# DRIVER.net
KiCad netlist of a schematic drawn in Altium Designer
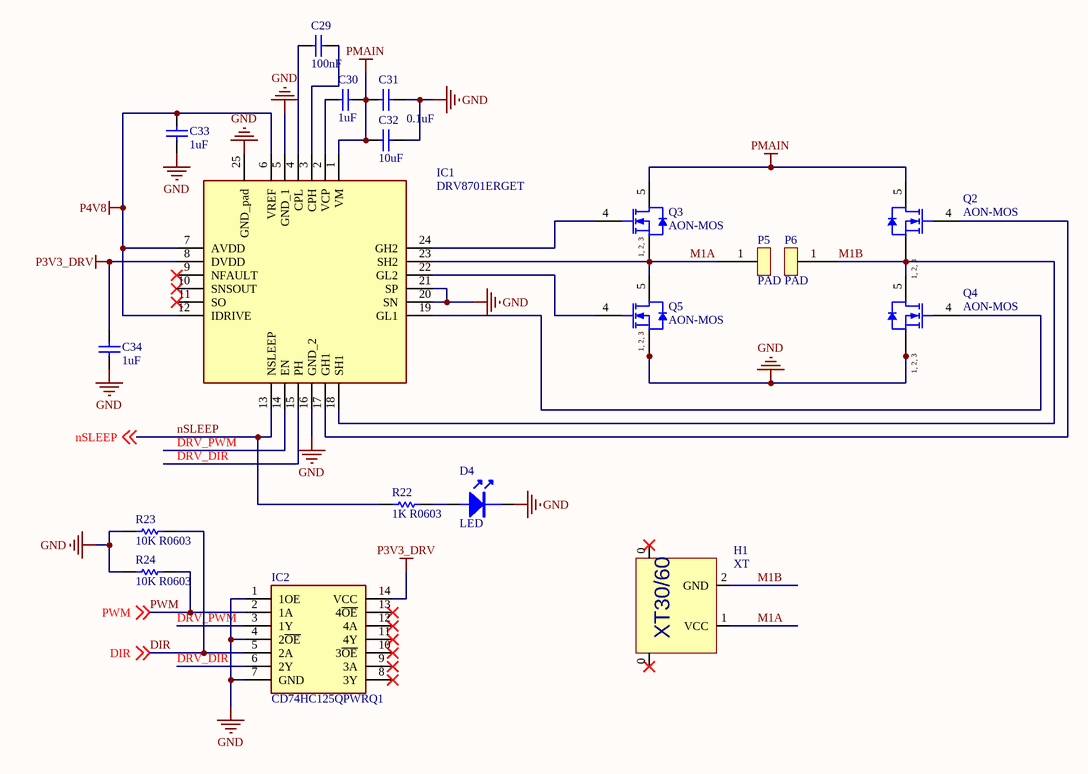
[diagram p0: DRIVER.SchDoc]

(export (version "E")
  (design (tool "Eeschema 10.0.6"))
  (components
    (comp (ref "C29")
      (value "100nF")
      (footprint "0603_C")
      (description "Capacitor")
      (fields (field (name "PUBLISHER") "Altium Limited"))
      (libsource (lib "My Footprint") (part "CAP"))
    )
    (comp (ref "C30")
      (value "1uF")
      (footprint "0603_C")
      (description "Capacitor")
      (fields (field (name "PUBLISHER") "Altium Limited"))
      (libsource (lib "My Footprint") (part "CAP"))
    )
    (comp (ref "C31")
      (value "0.1uF")
      (footprint "0603_C")
      (description "Capacitor")
      (fields (field (name "PUBLISHER") "Altium Limited"))
      (libsource (lib "My Footprint") (part "CAP"))
    )
    (comp (ref "C32")
      (value "10uF")
      (footprint "0805_c")
      (description "Capacitor")
      (fields (field (name "PUBLISHER") "Altium Limited"))
      (libsource (lib "My Footprint") (part "CAP"))
    )
    (comp (ref "C33")
      (value "1uF")
      (footprint "0603_C")
      (description "Capacitor")
      (fields (field (name "PUBLISHER") "Altium Limited"))
      (libsource (lib "My Footprint") (part "CAP"))
    )
    (comp (ref "C34")
      (value "1uF")
      (footprint "0603_C")
      (description "Capacitor")
      (fields (field (name "PUBLISHER") "Altium Limited"))
      (libsource (lib "My Footprint") (part "CAP"))
    )
    (comp (ref "D4")
      (value "LED")
      (footprint "0603_LED")
      (description "LED 发光二极管")
      (libsource (lib "My Footprint") (part "LED"))
    )
    (comp (ref "H1")
      (value "XT")
      (footprint "XT30PW-M")
      (libsource (lib "SamacSys") (part "XT_Connector_4pin"))
    )
    (comp (ref "IC1")
      (value "DRV8701ERGET")
      (footprint "QFN50P400X400X80-25N")
      (description "Integrated Circuit")
      (fields (field (name "MOUSER PART NUMBER") "595-DRV8701ERGET"))
      (libsource (lib "SamacSys") (part "DRV8701ERGET"))
    )
    (comp (ref "IC2")
      (value "CD74HC125QPWRQ1")
      (footprint "SOP65P640X120-14N")
      (description "Integrated Circuit")
      (fields (field (name "MOUSER PART NUMBER") "595-CD74HC125QPWRQ1"))
      (libsource (lib "SamacSys") (part "CD74HC125QPWRQ1"))
    )
    (comp (ref "P5") (value "PAD") (footprint "PAD") (libsource (lib "My Footprint") (part "PAD")))
    (comp (ref "P6") (value "PAD") (footprint "PAD") (libsource (lib "") (part "PAD_1")))
    (comp (ref "Q2") (value "AON-MOS") (footprint "so-8") (libsource (lib "My Footprint") (part "N-MOS-so")))
    (comp (ref "Q3") (value "AON-MOS") (footprint "so-8") (libsource (lib "My Footprint") (part "N-MOS-so")))
    (comp (ref "Q4") (value "AON-MOS") (footprint "so-8") (libsource (lib "My Footprint") (part "N-MOS-so")))
    (comp (ref "Q5") (value "AON-MOS") (footprint "so-8") (libsource (lib "My Footprint") (part "N-MOS-so")))
    (comp (ref "R22")
      (value "1K R0603")
      (footprint "0603_R")
      (description "Resistor")
      (fields (field (name "PUBLISHER") "Altium Limited"))
      (libsource (lib "My Footprint") (part "RES"))
    )
    (comp (ref "R23")
      (value "10K R0603")
      (footprint "0603_R")
      (description "Resistor")
      (fields (field (name "PUBLISHER") "Altium Limited"))
      (libsource (lib "My Footprint") (part "RES"))
    )
    (comp (ref "R24")
      (value "10K R0603")
      (footprint "0603_R")
      (description "Resistor")
      (fields (field (name "PUBLISHER") "Altium Limited"))
      (libsource (lib "My Footprint") (part "RES"))
    )
  )
  (nets
    (net (code "1") (name "/DRV_DIR") (class "Default")
      (node (ref "IC1") (pin "15") (pinfunction "PH_15") (pintype "passive"))
      (node (ref "IC2") (pin "6") (pinfunction "2Y_6") (pintype "passive"))
    )
    (net (code "2") (name "/DRV_PWM") (class "Default")
      (node (ref "IC1") (pin "14") (pinfunction "EN_14") (pintype "passive"))
      (node (ref "IC2") (pin "3") (pinfunction "1Y_3") (pintype "passive"))
    )
    (net (code "3") (name "/M1A") (class "Default")
      (node (ref "H1") (pin "1") (pinfunction "VCC_1") (pintype "power_in"))
      (node (ref "IC1") (pin "23") (pinfunction "SH2_23") (pintype "passive"))
      (node (ref "P5") (pin "1") (pintype "passive"))
      (node (ref "Q3") (pin "1") (pinfunction "S_1") (pintype "passive"))
      (node (ref "Q3") (pin "2") (pinfunction "S_2") (pintype "passive"))
      (node (ref "Q3") (pin "3") (pinfunction "S_3") (pintype "passive"))
      (node (ref "Q5") (pin "5") (pinfunction "D_5") (pintype "passive"))
    )
    (net (code "4") (name "/M1B") (class "Default")
      (node (ref "H1") (pin "2") (pinfunction "GND_2") (pintype "power_in"))
      (node (ref "IC1") (pin "18") (pinfunction "SH1_18") (pintype "passive"))
      (node (ref "P6") (pin "1") (pintype "passive"))
      (node (ref "Q2") (pin "1") (pinfunction "S_1") (pintype "passive"))
      (node (ref "Q2") (pin "2") (pinfunction "S_2") (pintype "passive"))
      (node (ref "Q2") (pin "3") (pinfunction "S_3") (pintype "passive"))
      (node (ref "Q4") (pin "5") (pinfunction "D_5") (pintype "passive"))
    )
    (net (code "5") (name "DIR") (class "Default")
      (node (ref "IC2") (pin "5") (pinfunction "2A_5") (pintype "passive"))
      (node (ref "R23") (pin "2") (pinfunction "2_2") (pintype "passive"))
    )
    (net (code "6") (name "GND") (class "Default")
      (node (ref "C31") (pin "2") (pinfunction "2_2") (pintype "passive"))
      (node (ref "C32") (pin "2") (pinfunction "2_2") (pintype "passive"))
      (node (ref "C33") (pin "2") (pinfunction "2_2") (pintype "passive"))
      (node (ref "C34") (pin "2") (pinfunction "2_2") (pintype "passive"))
      (node (ref "D4") (pin "2") (pinfunction "K_2") (pintype "passive"))
      (node (ref "IC1") (pin "16") (pinfunction "GND_2_16") (pintype "passive"))
      (node (ref "IC1") (pin "20") (pinfunction "SN_20") (pintype "passive"))
      (node (ref "IC1") (pin "21") (pinfunction "SP_21") (pintype "passive"))
      (node (ref "IC1") (pin "25") (pinfunction "GND_pad_25") (pintype "passive"))
      (node (ref "IC1") (pin "5") (pinfunction "GND_1_5") (pintype "passive"))
      (node (ref "IC2") (pin "1") (pinfunction "1OE_1") (pintype "passive"))
      (node (ref "IC2") (pin "4") (pinfunction "2~{OE}_4") (pintype "passive"))
      (node (ref "IC2") (pin "7") (pinfunction "GND_7") (pintype "passive"))
      (node (ref "Q4") (pin "1") (pinfunction "S_1") (pintype "passive"))
      (node (ref "Q4") (pin "2") (pinfunction "S_2") (pintype "passive"))
      (node (ref "Q4") (pin "3") (pinfunction "S_3") (pintype "passive"))
      (node (ref "Q5") (pin "1") (pinfunction "S_1") (pintype "passive"))
      (node (ref "Q5") (pin "2") (pinfunction "S_2") (pintype "passive"))
      (node (ref "Q5") (pin "3") (pinfunction "S_3") (pintype "passive"))
      (node (ref "R23") (pin "1") (pinfunction "1_1") (pintype "passive"))
      (node (ref "R24") (pin "2") (pinfunction "2_2") (pintype "passive"))
    )
    (net (code "7") (name "Net-(D4-A)") (class "Default")
      (node (ref "D4") (pin "1") (pinfunction "A_1") (pintype "passive"))
      (node (ref "R22") (pin "2") (pinfunction "2_2") (pintype "passive"))
    )
    (net (code "8") (name "Net-(IC1-CPH)") (class "Default")
      (node (ref "C29") (pin "2") (pinfunction "2_2") (pintype "passive"))
      (node (ref "IC1") (pin "3") (pinfunction "CPH_3") (pintype "passive"))
    )
    (net (code "9") (name "Net-(IC1-CPL)") (class "Default")
      (node (ref "C29") (pin "1") (pinfunction "1_1") (pintype "passive"))
      (node (ref "IC1") (pin "4") (pinfunction "CPL_4") (pintype "passive"))
    )
    (net (code "10") (name "Net-(IC1-GH1)") (class "Default")
      (node (ref "IC1") (pin "17") (pinfunction "GH1_17") (pintype "passive"))
      (node (ref "Q2") (pin "4") (pinfunction "G_4") (pintype "passive"))
    )
    (net (code "11") (name "Net-(IC1-GH2)") (class "Default")
      (node (ref "IC1") (pin "24") (pinfunction "GH2_24") (pintype "passive"))
      (node (ref "Q3") (pin "4") (pinfunction "G_4") (pintype "passive"))
    )
    (net (code "12") (name "Net-(IC1-GL1)") (class "Default")
      (node (ref "IC1") (pin "19") (pinfunction "GL1_19") (pintype "passive"))
      (node (ref "Q4") (pin "4") (pinfunction "G_4") (pintype "passive"))
    )
    (net (code "13") (name "Net-(IC1-GL2)") (class "Default")
      (node (ref "IC1") (pin "22") (pinfunction "GL2_22") (pintype "passive"))
      (node (ref "Q5") (pin "4") (pinfunction "G_4") (pintype "passive"))
    )
    (net (code "14") (name "Net-(IC1-VCP)") (class "Default")
      (node (ref "C30") (pin "1") (pinfunction "1_1") (pintype "passive"))
      (node (ref "IC1") (pin "2") (pinfunction "VCP_2") (pintype "passive"))
    )
    (net (code "15") (name "P3V3_DRV") (class "Default")
      (node (ref "C34") (pin "1") (pinfunction "1_1") (pintype "passive"))
      (node (ref "IC1") (pin "8") (pinfunction "DVDD_8") (pintype "passive"))
      (node (ref "IC2") (pin "14") (pinfunction "VCC_14") (pintype "passive"))
    )
    (net (code "16") (name "P4V8") (class "Default")
      (node (ref "C33") (pin "1") (pinfunction "1_1") (pintype "passive"))
      (node (ref "IC1") (pin "12") (pinfunction "IDRIVE_12") (pintype "passive"))
      (node (ref "IC1") (pin "6") (pinfunction "VREF_6") (pintype "passive"))
      (node (ref "IC1") (pin "7") (pinfunction "AVDD_7") (pintype "passive"))
    )
    (net (code "17") (name "PMAIN") (class "Default")
      (node (ref "C30") (pin "2") (pinfunction "2_2") (pintype "passive"))
      (node (ref "C31") (pin "1") (pinfunction "1_1") (pintype "passive"))
      (node (ref "C32") (pin "1") (pinfunction "1_1") (pintype "passive"))
      (node (ref "IC1") (pin "1") (pinfunction "VM_1") (pintype "passive"))
      (node (ref "Q2") (pin "5") (pinfunction "D_5") (pintype "passive"))
      (node (ref "Q3") (pin "5") (pinfunction "D_5") (pintype "passive"))
    )
    (net (code "18") (name "PWM") (class "Default")
      (node (ref "IC2") (pin "2") (pinfunction "1A_2") (pintype "passive"))
      (node (ref "R24") (pin "1") (pinfunction "1_1") (pintype "passive"))
    )
    (net (code "19") (name "nSLEEP") (class "Default")
      (node (ref "IC1") (pin "13") (pinfunction "NSLEEP_13") (pintype "passive"))
      (node (ref "R22") (pin "1") (pinfunction "1_1") (pintype "passive"))
    )
    (net (code "20") (name "unconnected-(H1-CONN-Pad0)") (class "Default")
      (node (ref "H1") (pin "0") (pinfunction "CONN_0") (pintype "power_in+no_connect"))
    )
    (net (code "21") (name "unconnected-(H1-CONN-Pad0)_1") (class "Default")
      (node (ref "H1") (pin "0") (pinfunction "CONN_0") (pintype "power_in+no_connect"))
    )
    (net (code "22") (name "unconnected-(IC1-NFAULT-Pad9)") (class "Default")
      (node (ref "IC1") (pin "9") (pinfunction "NFAULT_9") (pintype "passive+no_connect"))
    )
    (net (code "23") (name "unconnected-(IC1-SNSOUT-Pad10)") (class "Default")
      (node (ref "IC1") (pin "10") (pinfunction "SNSOUT_10") (pintype "passive+no_connect"))
    )
    (net (code "24") (name "unconnected-(IC1-SO-Pad11)") (class "Default")
      (node (ref "IC1") (pin "11") (pinfunction "SO_11") (pintype "passive+no_connect"))
    )
    (net (code "25") (name "unconnected-(IC2-3A-Pad9)") (class "Default")
      (node (ref "IC2") (pin "9") (pinfunction "3A_9") (pintype "passive+no_connect"))
    )
    (net (code "26") (name "unconnected-(IC2-3Y-Pad8)") (class "Default")
      (node (ref "IC2") (pin "8") (pinfunction "3Y_8") (pintype "passive+no_connect"))
    )
    (net (code "27") (name "unconnected-(IC2-3~{OE}-Pad10)") (class "Default")
      (node (ref "IC2") (pin "10") (pinfunction "3~{OE}_10") (pintype "passive+no_connect"))
    )
    (net (code "28") (name "unconnected-(IC2-4A-Pad12)") (class "Default")
      (node (ref "IC2") (pin "12") (pinfunction "4A_12") (pintype "passive+no_connect"))
    )
    (net (code "29") (name "unconnected-(IC2-4Y-Pad11)") (class "Default")
      (node (ref "IC2") (pin "11") (pinfunction "4Y_11") (pintype "passive+no_connect"))
    )
    (net (code "30") (name "unconnected-(IC2-4~{OE}-Pad13)") (class "Default")
      (node (ref "IC2") (pin "13") (pinfunction "4~{OE}_13") (pintype "passive+no_connect"))
    )
  )
)
